# Y-babies_--_PicAxe_v_1_3.net
KiCad netlist of a schematic drawn in EAGLE
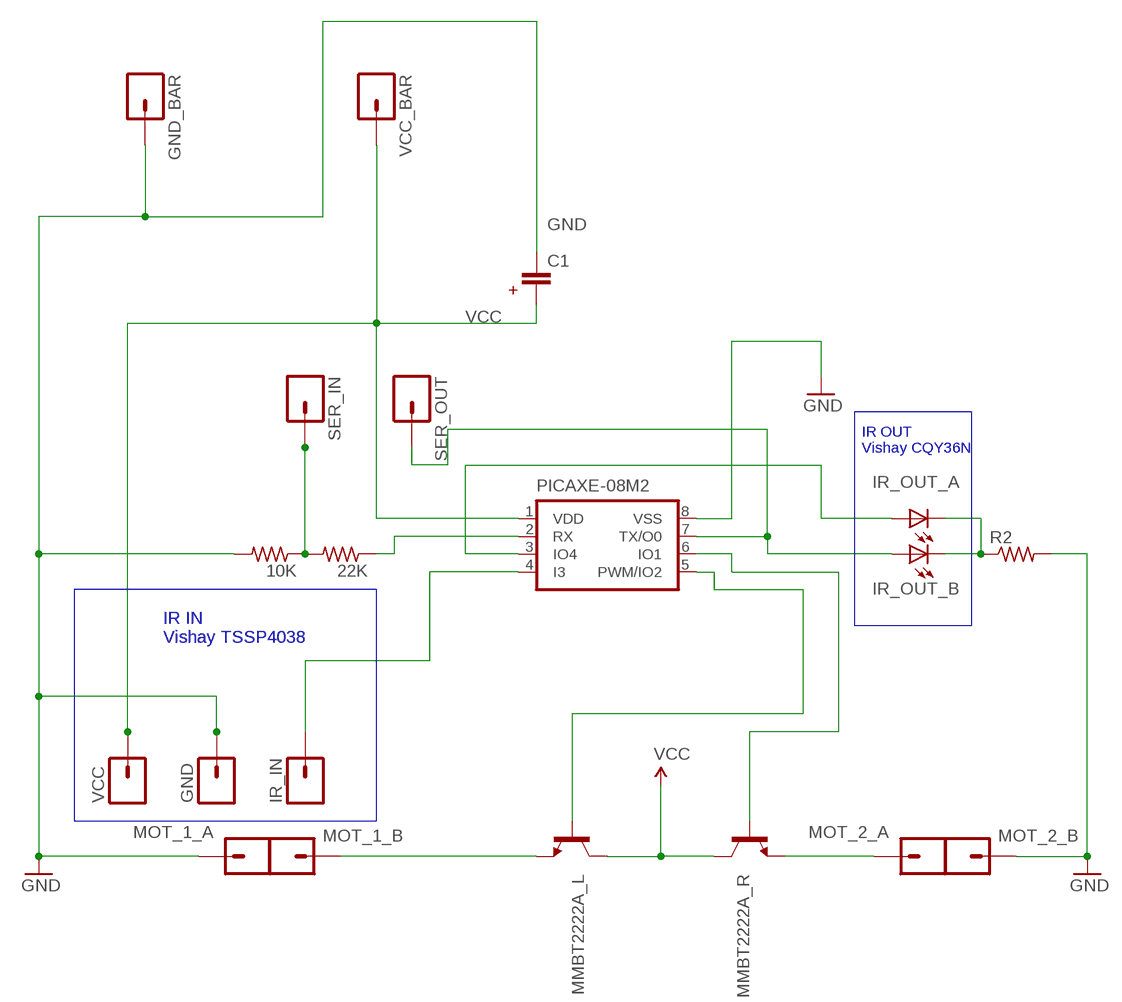
[diagram p0: schematic, sheet 1]

(export (version "E")
  (design (tool "Eeschema 10.0.6"))
  (components
    (comp (ref "10K")
      (value "R-US_R0805W")
      (footprint "eagle-import:R0805W")
      (libsource (lib "eagle-import") (part "R-US_R0805W"))
    )
    (comp (ref "22K")
      (value "R-US_R0805W")
      (footprint "eagle-import:R0805W")
      (libsource (lib "eagle-import") (part "R-US_R0805W"))
    )
    (comp (ref "C1")
      (value "CAPPTH1")
      (footprint "eagle-import:CAP-PTH-5MM")
      (libsource (lib "eagle-import") (part "CAPPTH1"))
    )
    (comp (ref "GND")
      (value "M01PTH")
      (footprint "eagle-import:1X01")
      (libsource (lib "eagle-import") (part "M01PTH"))
    )
    (comp (ref "GND_BAR")
      (value "M01PTH")
      (footprint "eagle-import:1X01")
      (libsource (lib "eagle-import") (part "M01PTH"))
    )
    (comp (ref "IR_IN")
      (value "M01PTH")
      (footprint "eagle-import:1X01")
      (libsource (lib "eagle-import") (part "M01PTH"))
    )
    (comp (ref "IR_OUT_A")
      (value "LED3MM")
      (footprint "eagle-import:LED3MM")
      (libsource (lib "eagle-import") (part "LED3MM"))
    )
    (comp (ref "IR_OUT_B")
      (value "LED3MM")
      (footprint "eagle-import:LED3MM")
      (libsource (lib "eagle-import") (part "LED3MM"))
    )
    (comp (ref "MMBT2222A_L")
      (value "TRANSISTOR_NPNSOT23")
      (footprint "eagle-import:SOT23")
      (libsource (lib "eagle-import") (part "TRANSISTOR_NPNSOT23"))
    )
    (comp (ref "MMBT2222A_R")
      (value "TRANSISTOR_NPNSOT23")
      (footprint "eagle-import:SOT23")
      (libsource (lib "eagle-import") (part "TRANSISTOR_NPNSOT23"))
    )
    (comp (ref "MOT_1_A")
      (value "M01SMD-4.5X1.5")
      (footprint "eagle-import:PAD-1.5X4.5")
      (libsource (lib "eagle-import") (part "M01SMD-4.5X1.5"))
    )
    (comp (ref "MOT_1_B")
      (value "M01SMD-4.5X1.5")
      (footprint "eagle-import:PAD-1.5X4.5")
      (libsource (lib "eagle-import") (part "M01SMD-4.5X1.5"))
    )
    (comp (ref "MOT_2_A")
      (value "M01SMD-4.5X1.5")
      (footprint "eagle-import:PAD-1.5X4.5")
      (libsource (lib "eagle-import") (part "M01SMD-4.5X1.5"))
    )
    (comp (ref "MOT_2_B")
      (value "M01SMD-4.5X1.5")
      (footprint "eagle-import:PAD-1.5X4.5")
      (libsource (lib "eagle-import") (part "M01SMD-4.5X1.5"))
    )
    (comp (ref "PICAXE-08M2")
      (value "PICAXE-08M2")
      (footprint "eagle-import:DIL8")
      (libsource (lib "eagle-import") (part "PICAXE-08M"))
    )
    (comp (ref "R2")
      (value "R-US_R0805W")
      (footprint "eagle-import:R0805W")
      (libsource (lib "eagle-import") (part "R-US_R0805W"))
    )
    (comp (ref "SER_IN")
      (value "M01PTH")
      (footprint "eagle-import:1X01")
      (libsource (lib "eagle-import") (part "M01PTH"))
    )
    (comp (ref "SER_OUT")
      (value "M01PTH")
      (footprint "eagle-import:1X01")
      (libsource (lib "eagle-import") (part "M01PTH"))
    )
    (comp (ref "VCC")
      (value "M01PTH")
      (footprint "eagle-import:1X01")
      (libsource (lib "eagle-import") (part "M01PTH"))
    )
    (comp (ref "VCC_BAR")
      (value "M01PTH")
      (footprint "eagle-import:1X01")
      (libsource (lib "eagle-import") (part "M01PTH"))
    )
  )
  (nets
    (net (code "1") (name "GND") (class "Default")
      (node (ref "10K") (pin "2") (pinfunction "2_2") (pintype "passive"))
      (node (ref "C1") (pin "1") (pinfunction "1_1") (pintype "passive"))
      (node (ref "GND") (pin "1") (pinfunction "1_1") (pintype "passive"))
      (node (ref "GND_BAR") (pin "1") (pinfunction "1_1") (pintype "passive"))
      (node (ref "MOT_1_A") (pin "P$1") (pinfunction "1_P$1") (pintype "passive"))
      (node (ref "MOT_2_B") (pin "P$1") (pinfunction "1_P$1") (pintype "passive"))
      (node (ref "PICAXE-08M2") (pin "8") (pinfunction "VSS_8") (pintype "power_in"))
      (node (ref "R2") (pin "2") (pinfunction "2_2") (pintype "passive"))
    )
    (net (code "2") (name "Net-(10K-Pad1)") (class "Default")
      (node (ref "10K") (pin "1") (pinfunction "1_1") (pintype "passive"))
      (node (ref "22K") (pin "2") (pinfunction "2_2") (pintype "passive"))
      (node (ref "SER_IN") (pin "1") (pinfunction "1_1") (pintype "passive"))
    )
    (net (code "3") (name "Net-(IR_OUT_A-C)") (class "Default")
      (node (ref "IR_OUT_A") (pin "K") (pinfunction "C_K") (pintype "passive"))
      (node (ref "IR_OUT_B") (pin "K") (pinfunction "C_K") (pintype "passive"))
      (node (ref "R2") (pin "1") (pinfunction "1_1") (pintype "passive"))
    )
    (net (code "4") (name "Net-(MMBT2222A_L-B)") (class "Default")
      (node (ref "MMBT2222A_L") (pin "1") (pinfunction "B_1") (pintype "passive"))
      (node (ref "PICAXE-08M2") (pin "5") (pinfunction "PWM/IO2_5") (pintype "bidirectional"))
    )
    (net (code "5") (name "Net-(MMBT2222A_L-E)") (class "Default")
      (node (ref "MMBT2222A_L") (pin "2") (pinfunction "E_2") (pintype "passive"))
      (node (ref "MOT_1_B") (pin "P$1") (pinfunction "1_P$1") (pintype "passive"))
    )
    (net (code "6") (name "Net-(MMBT2222A_R-B)") (class "Default")
      (node (ref "MMBT2222A_R") (pin "1") (pinfunction "B_1") (pintype "passive"))
      (node (ref "PICAXE-08M2") (pin "6") (pinfunction "IO1_6") (pintype "bidirectional"))
    )
    (net (code "7") (name "Net-(MMBT2222A_R-E)") (class "Default")
      (node (ref "MMBT2222A_R") (pin "2") (pinfunction "E_2") (pintype "passive"))
      (node (ref "MOT_2_A") (pin "P$1") (pinfunction "1_P$1") (pintype "passive"))
    )
    (net (code "8") (name "Net-(PICAXE-08M2-I3)") (class "Default")
      (node (ref "IR_IN") (pin "1") (pinfunction "1_1") (pintype "passive"))
      (node (ref "PICAXE-08M2") (pin "4") (pinfunction "I3_4") (pintype "input"))
    )
    (net (code "9") (name "Net-(PICAXE-08M2-IO4)") (class "Default")
      (node (ref "IR_OUT_A") (pin "A") (pinfunction "A_A") (pintype "passive"))
      (node (ref "PICAXE-08M2") (pin "3") (pinfunction "IO4_3") (pintype "bidirectional"))
    )
    (net (code "10") (name "Net-(PICAXE-08M2-RX)") (class "Default")
      (node (ref "22K") (pin "1") (pinfunction "1_1") (pintype "passive"))
      (node (ref "PICAXE-08M2") (pin "2") (pinfunction "RX_2") (pintype "input"))
    )
    (net (code "11") (name "Net-(PICAXE-08M2-TX{slash}O0)") (class "Default")
      (node (ref "IR_OUT_B") (pin "A") (pinfunction "A_A") (pintype "passive"))
      (node (ref "PICAXE-08M2") (pin "7") (pinfunction "TX/O0_7") (pintype "output"))
      (node (ref "SER_OUT") (pin "1") (pinfunction "1_1") (pintype "passive"))
    )
    (net (code "12") (name "VCC") (class "Default")
      (node (ref "C1") (pin "2") (pinfunction "2_2") (pintype "passive"))
      (node (ref "MMBT2222A_L") (pin "3") (pinfunction "C_3") (pintype "passive"))
      (node (ref "MMBT2222A_R") (pin "3") (pinfunction "C_3") (pintype "passive"))
      (node (ref "PICAXE-08M2") (pin "1") (pinfunction "VDD_1") (pintype "power_in"))
      (node (ref "VCC") (pin "1") (pinfunction "1_1") (pintype "passive"))
      (node (ref "VCC_BAR") (pin "1") (pinfunction "1_1") (pintype "passive"))
    )
  )
)
